# Flash.net
KiCad netlist of a schematic drawn in Altium Designer
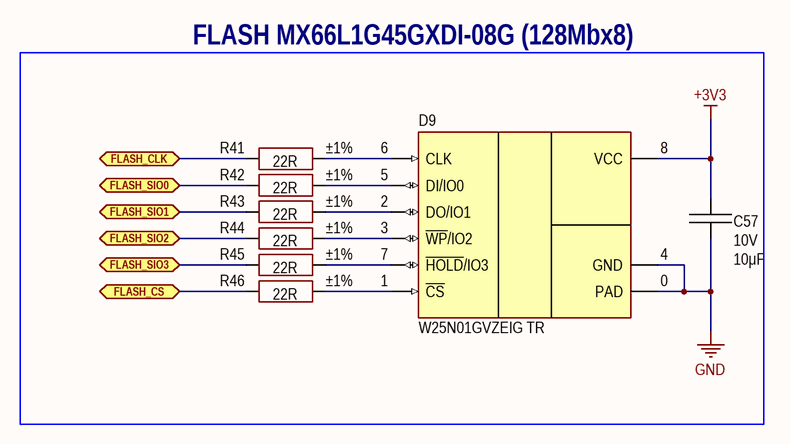
[diagram p0: Flash.SchDoc]

(export (version "E")
  (design (tool "Eeschema 10.0.6"))
  (components
    (comp (ref "C57")
      (value "10μF")
      (footprint "CAP: 0805")
      (description "10 µF ±10% 10V Ceramic Capacitor X7R 0805 (2012 Metric)")
      (fields
        (field (name "MANUFACTURER") "Yageo")
        (field (name "PARTNUMBER") "CC0805KFX7R6BB106")
        (field (name "VOLTAGE") "10V")
      )
      (libsource (lib "capacitor") (part "Ceramic_0805"))
    )
    (comp (ref "D9")
      (value "~")
      (footprint "IC: 8-WSON")
      (description "FLASH")
      (fields
        (field (name "MANUFACTURER") "Winbond Electronics")
        (field (name "VALUEMANUFACTURERPARTNUMBER") "IC memory, FLASH, 1gb (128M x 8), 133 MHz, SPI/QuadSPI, 2.7...3.6V, -40...+85°C, 8-WDFN")
        (field (name "PARTNUMBER") "W25N01GVZEIG TR")
      )
      (libsource (lib "MyLib") (part "W25N01GVZEIG TR"))
    )
    (comp (ref "R41")
      (value "22R")
      (footprint "RES: 0805")
      (description "22 Ohms ±1% 0.125W, 1/8W Chip Resistor 0805 (2012 Metric) Moisture Resistant Thick Film")
      (fields
        (field (name "MANUFACTURER") "Yageo")
        (field (name "PARTNUMBER") "RC0805FR-0722RL")
        (field (name "TOLERANCE") "±1%")
      )
      (libsource (lib "resistor") (part "Resistor_0805"))
    )
    (comp (ref "R42")
      (value "22R")
      (footprint "RES: 0805")
      (description "22 Ohms ±1% 0.125W, 1/8W Chip Resistor 0805 (2012 Metric) Moisture Resistant Thick Film")
      (fields
        (field (name "MANUFACTURER") "Yageo")
        (field (name "PARTNUMBER") "RC0805FR-0722RL")
        (field (name "TOLERANCE") "±1%")
      )
      (libsource (lib "resistor") (part "Resistor_0805"))
    )
    (comp (ref "R43")
      (value "22R")
      (footprint "RES: 0805")
      (description "22 Ohms ±1% 0.125W, 1/8W Chip Resistor 0805 (2012 Metric) Moisture Resistant Thick Film")
      (fields
        (field (name "MANUFACTURER") "Yageo")
        (field (name "PARTNUMBER") "RC0805FR-0722RL")
        (field (name "TOLERANCE") "±1%")
      )
      (libsource (lib "resistor") (part "Resistor_0805"))
    )
    (comp (ref "R44")
      (value "22R")
      (footprint "RES: 0805")
      (description "22 Ohms ±1% 0.125W, 1/8W Chip Resistor 0805 (2012 Metric) Moisture Resistant Thick Film")
      (fields
        (field (name "MANUFACTURER") "Yageo")
        (field (name "PARTNUMBER") "RC0805FR-0722RL")
        (field (name "TOLERANCE") "±1%")
      )
      (libsource (lib "resistor") (part "Resistor_0805"))
    )
    (comp (ref "R45")
      (value "22R")
      (footprint "RES: 0805")
      (description "22 Ohms ±1% 0.125W, 1/8W Chip Resistor 0805 (2012 Metric) Moisture Resistant Thick Film")
      (fields
        (field (name "MANUFACTURER") "Yageo")
        (field (name "PARTNUMBER") "RC0805FR-0722RL")
        (field (name "TOLERANCE") "±1%")
      )
      (libsource (lib "resistor") (part "Resistor_0805"))
    )
    (comp (ref "R46")
      (value "22R")
      (footprint "RES: 0805")
      (description "22 Ohms ±1% 0.125W, 1/8W Chip Resistor 0805 (2012 Metric) Moisture Resistant Thick Film")
      (fields
        (field (name "MANUFACTURER") "Yageo")
        (field (name "PARTNUMBER") "RC0805FR-0722RL")
        (field (name "TOLERANCE") "±1%")
      )
      (libsource (lib "resistor") (part "Resistor_0805"))
    )
  )
  (nets
    (net (code "1") (name "+3V3") (class "Default")
      (node (ref "C57") (pin "2") (pinfunction "2_2") (pintype "passive"))
      (node (ref "D9") (pin "8") (pinfunction "VCC_8") (pintype "power_in"))
    )
    (net (code "2") (name "/FLASH_CLK") (class "Default")
      (node (ref "R41") (pin "1") (pinfunction "1_1") (pintype "passive"))
    )
    (net (code "3") (name "/FLASH_CS") (class "Default")
      (node (ref "R46") (pin "1") (pinfunction "1_1") (pintype "passive"))
    )
    (net (code "4") (name "/FLASH_SIO0") (class "Default")
      (node (ref "R42") (pin "1") (pinfunction "1_1") (pintype "passive"))
    )
    (net (code "5") (name "/FLASH_SIO1") (class "Default")
      (node (ref "R43") (pin "1") (pinfunction "1_1") (pintype "passive"))
    )
    (net (code "6") (name "/FLASH_SIO2") (class "Default")
      (node (ref "R44") (pin "1") (pinfunction "1_1") (pintype "passive"))
    )
    (net (code "7") (name "/FLASH_SIO3") (class "Default")
      (node (ref "R45") (pin "1") (pinfunction "1_1") (pintype "passive"))
    )
    (net (code "8") (name "GND") (class "Default")
      (node (ref "C57") (pin "1") (pinfunction "1_1") (pintype "passive"))
      (node (ref "D9") (pin "0") (pinfunction "PAD_0") (pintype "power_in"))
      (node (ref "D9") (pin "4") (pinfunction "GND_4") (pintype "power_in"))
    )
    (net (code "9") (name "Net-(D9-CLK)") (class "Default")
      (node (ref "D9") (pin "6") (pinfunction "CLK_6") (pintype "input"))
      (node (ref "R41") (pin "2") (pinfunction "2_2") (pintype "passive"))
    )
    (net (code "10") (name "Net-(D9-DI{slash}IO0)") (class "Default")
      (node (ref "D9") (pin "5") (pinfunction "DI/IO0_5") (pintype "bidirectional"))
      (node (ref "R42") (pin "2") (pinfunction "2_2") (pintype "passive"))
    )
    (net (code "11") (name "Net-(D9-DO{slash}IO1)") (class "Default")
      (node (ref "D9") (pin "2") (pinfunction "DO/IO1_2") (pintype "bidirectional"))
      (node (ref "R43") (pin "2") (pinfunction "2_2") (pintype "passive"))
    )
    (net (code "12") (name "Net-(D9-~{CS})") (class "Default")
      (node (ref "D9") (pin "1") (pinfunction "~{CS}_1") (pintype "input"))
      (node (ref "R46") (pin "2") (pinfunction "2_2") (pintype "passive"))
    )
    (net (code "13") (name "Net-(D9-~{HOLD}{slash}IO3)") (class "Default")
      (node (ref "D9") (pin "7") (pinfunction "~{HOLD}/IO3_7") (pintype "bidirectional"))
      (node (ref "R45") (pin "2") (pinfunction "2_2") (pintype "passive"))
    )
    (net (code "14") (name "Net-(D9-~{WP}{slash}IO2)") (class "Default")
      (node (ref "D9") (pin "3") (pinfunction "~{WP}/IO2_3") (pintype "bidirectional"))
      (node (ref "R44") (pin "2") (pinfunction "2_2") (pintype "passive"))
    )
  )
)
